# Sheet3.net
KiCad netlist of a schematic drawn in Altium Designer
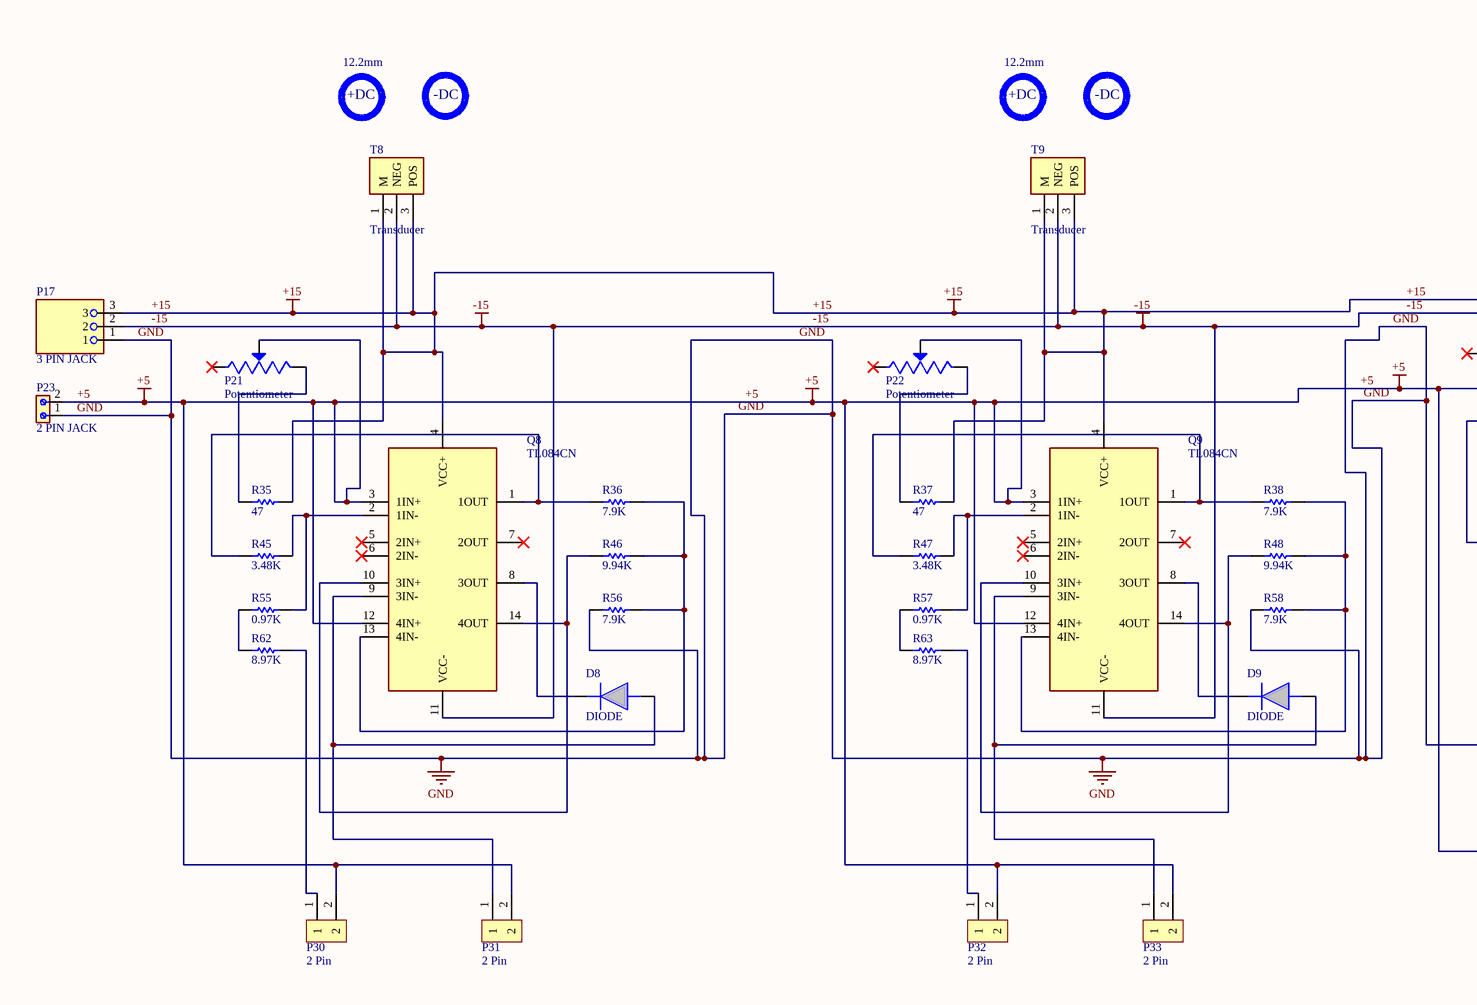
[diagram p0: Sheet3.SchDoc, left]
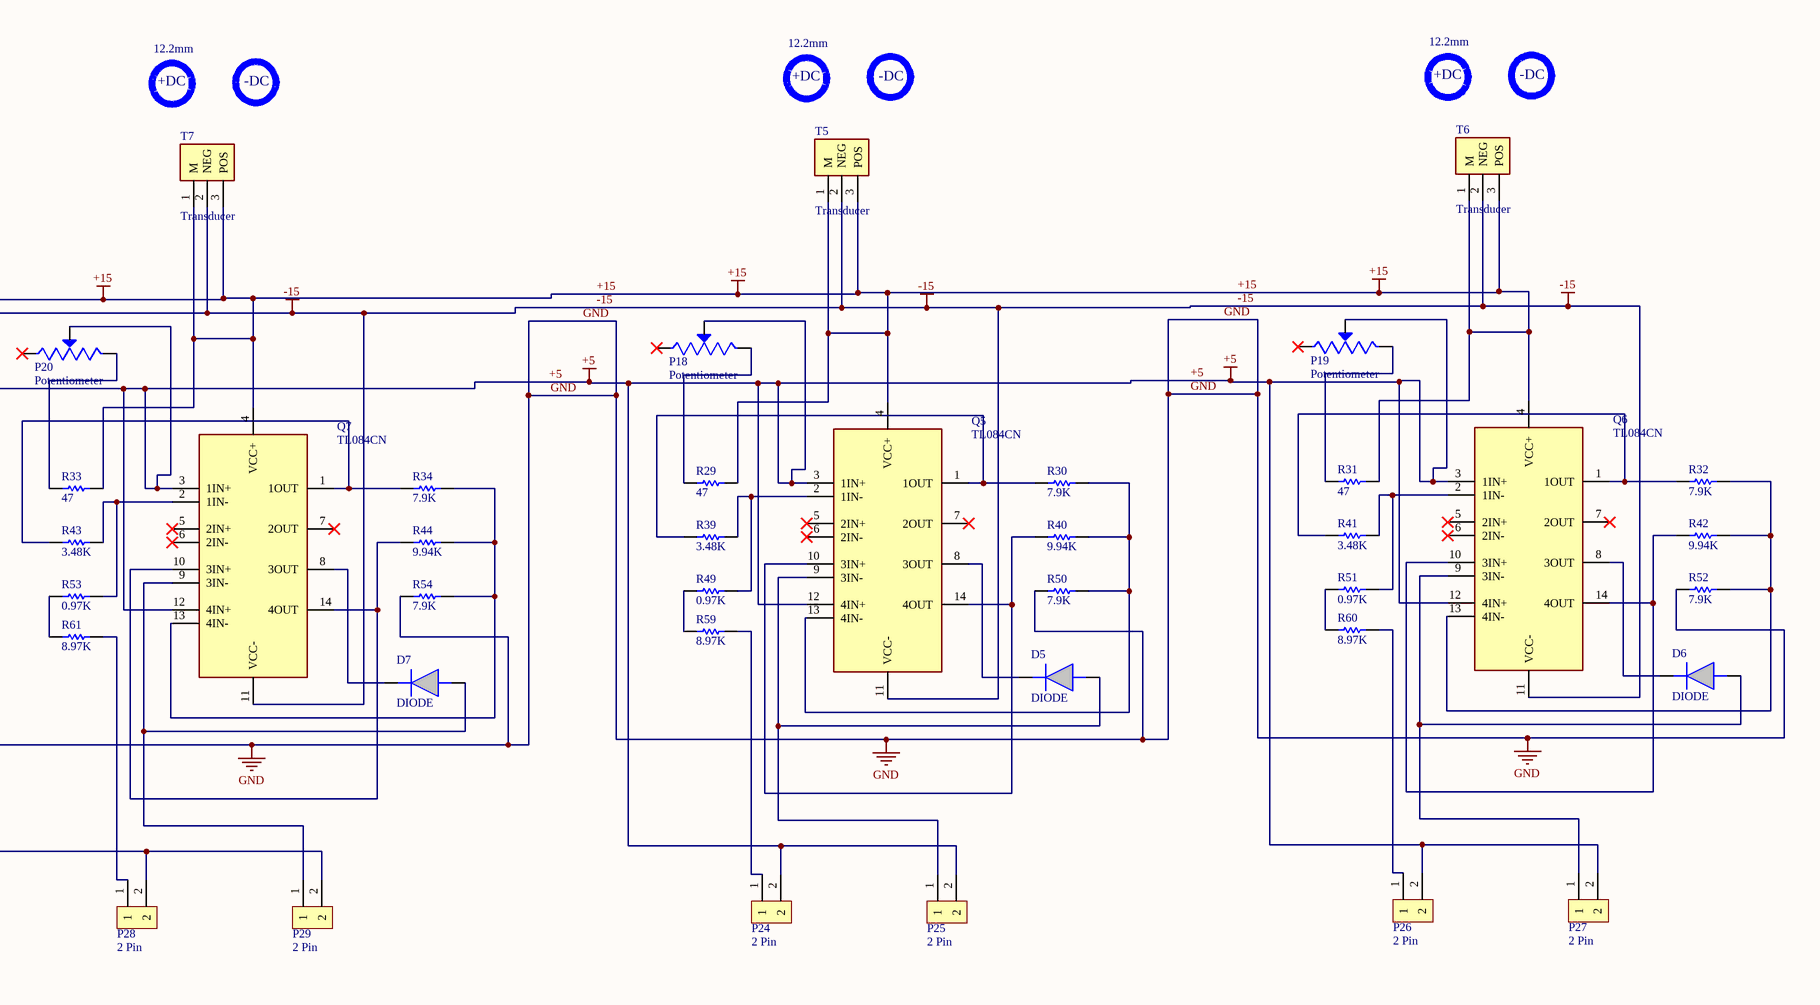
[diagram p1: Sheet3.SchDoc, right]

(export (version "E")
  (design (tool "Eeschema 10.0.6"))
  (components
    (comp (ref "D5")
      (value "DIODE")
      (footprint "Diode")
      (description "1N4007S")
      (libsource (lib "Schlib1") (part "DIODE"))
    )
    (comp (ref "D6")
      (value "DIODE")
      (footprint "Diode")
      (description "1N4007S")
      (libsource (lib "Schlib1") (part "DIODE"))
    )
    (comp (ref "D7")
      (value "DIODE")
      (footprint "Diode")
      (description "1N4007S")
      (libsource (lib "Schlib1") (part "DIODE"))
    )
    (comp (ref "D8")
      (value "DIODE")
      (footprint "Diode")
      (description "1N4007S")
      (libsource (lib "Schlib1") (part "DIODE"))
    )
    (comp (ref "D9")
      (value "DIODE")
      (footprint "Diode")
      (description "1N4007S")
      (libsource (lib "Schlib1") (part "DIODE"))
    )
    (comp (ref "P17")
      (value "3 PIN JACK")
      (footprint "3 PIN JACK")
      (libsource (lib "Schlib1") (part "3 PIN JACK"))
    )
    (comp (ref "P18")
      (value "Potentiometer")
      (footprint "Potentiometer")
      (libsource (lib "Schlib1") (part "Potentiometer"))
    )
    (comp (ref "P19")
      (value "Potentiometer")
      (footprint "Potentiometer")
      (libsource (lib "Schlib1") (part "Potentiometer"))
    )
    (comp (ref "P20")
      (value "Potentiometer")
      (footprint "Potentiometer")
      (libsource (lib "Schlib1") (part "Potentiometer"))
    )
    (comp (ref "P21")
      (value "Potentiometer")
      (footprint "Potentiometer")
      (libsource (lib "Schlib1") (part "Potentiometer"))
    )
    (comp (ref "P22")
      (value "Potentiometer")
      (footprint "Potentiometer")
      (libsource (lib "Schlib1") (part "Potentiometer"))
    )
    (comp (ref "P23")
      (value "2 PIN JACK")
      (footprint "2 PIN JACK")
      (libsource (lib "Schlib1") (part "2 PIN JACK"))
    )
    (comp (ref "P24")
      (value "2 Pin")
      (footprint "2 PIN")
      (description "22272021")
      (libsource (lib "Schlib1") (part "2 Pin"))
    )
    (comp (ref "P25")
      (value "2 Pin")
      (footprint "2 PIN")
      (description "22272021")
      (libsource (lib "Schlib1") (part "2 Pin"))
    )
    (comp (ref "P26")
      (value "2 Pin")
      (footprint "2 PIN")
      (description "22272021")
      (libsource (lib "Schlib1") (part "2 Pin"))
    )
    (comp (ref "P27")
      (value "2 Pin")
      (footprint "2 PIN")
      (description "22272021")
      (libsource (lib "Schlib1") (part "2 Pin"))
    )
    (comp (ref "P28")
      (value "2 Pin")
      (footprint "2 PIN")
      (description "22272021")
      (libsource (lib "Schlib1") (part "2 Pin"))
    )
    (comp (ref "P29")
      (value "2 Pin")
      (footprint "2 PIN")
      (description "22272021")
      (libsource (lib "Schlib1") (part "2 Pin"))
    )
    (comp (ref "P30")
      (value "2 Pin")
      (footprint "2 PIN")
      (description "22272021")
      (libsource (lib "Schlib1") (part "2 Pin"))
    )
    (comp (ref "P31")
      (value "2 Pin")
      (footprint "2 PIN")
      (description "22272021")
      (libsource (lib "Schlib1") (part "2 Pin"))
    )
    (comp (ref "P32")
      (value "2 Pin")
      (footprint "2 PIN")
      (description "22272021")
      (libsource (lib "Schlib1") (part "2 Pin"))
    )
    (comp (ref "P33")
      (value "2 Pin")
      (footprint "2 PIN")
      (description "22272021")
      (libsource (lib "Schlib1") (part "2 Pin"))
    )
    (comp (ref "Q5") (value "TL084CN") (footprint "TL084CN") (libsource (lib "Schlib1") (part "TL084CN")))
    (comp (ref "Q6") (value "TL084CN") (footprint "TL084CN") (libsource (lib "Schlib1") (part "TL084CN")))
    (comp (ref "Q7") (value "TL084CN") (footprint "TL084CN") (libsource (lib "Schlib1") (part "TL084CN")))
    (comp (ref "Q8") (value "TL084CN") (footprint "TL084CN") (libsource (lib "Schlib1") (part "TL084CN")))
    (comp (ref "Q9") (value "TL084CN") (footprint "TL084CN") (libsource (lib "Schlib1") (part "TL084CN")))
    (comp (ref "R29")
      (value "47")
      (footprint "47")
      (description "MFR-25FRF52-47R")
      (libsource (lib "Schlib1") (part "47"))
    )
    (comp (ref "R30")
      (value "7.9K")
      (footprint "7.90K")
      (description "MFR-25FBF52-7K87")
      (libsource (lib "Schlib1") (part "7.9K"))
    )
    (comp (ref "R31")
      (value "47")
      (footprint "47")
      (description "MFR-25FRF52-47R")
      (libsource (lib "Schlib1") (part "47"))
    )
    (comp (ref "R32")
      (value "7.9K")
      (footprint "7.90K")
      (description "MFR-25FBF52-7K87")
      (libsource (lib "Schlib1") (part "7.9K"))
    )
    (comp (ref "R33")
      (value "47")
      (footprint "47")
      (description "MFR-25FRF52-47R")
      (libsource (lib "Schlib1") (part "47"))
    )
    (comp (ref "R34")
      (value "7.9K")
      (footprint "7.90K")
      (description "MFR-25FBF52-7K87")
      (libsource (lib "Schlib1") (part "7.9K"))
    )
    (comp (ref "R35")
      (value "47")
      (footprint "47")
      (description "MFR-25FRF52-47R")
      (libsource (lib "Schlib1") (part "47"))
    )
    (comp (ref "R36")
      (value "7.9K")
      (footprint "7.90K")
      (description "MFR-25FBF52-7K87")
      (libsource (lib "Schlib1") (part "7.9K"))
    )
    (comp (ref "R37")
      (value "47")
      (footprint "47")
      (description "MFR-25FRF52-47R")
      (libsource (lib "Schlib1") (part "47"))
    )
    (comp (ref "R38")
      (value "7.9K")
      (footprint "7.90K")
      (description "MFR-25FBF52-7K87")
      (libsource (lib "Schlib1") (part "7.9K"))
    )
    (comp (ref "R39")
      (value "3.48K")
      (footprint "3.48K")
      (description "MFR-25FBF52-3K48")
      (libsource (lib "Schlib1") (part "3.48K"))
    )
    (comp (ref "R40")
      (value "9.94K")
      (footprint "9.94K")
      (description "MFR-25FTE52-9K76")
      (libsource (lib "Schlib1") (part "9.94K"))
    )
    (comp (ref "R41")
      (value "3.48K")
      (footprint "3.48K")
      (description "MFR-25FBF52-3K48")
      (libsource (lib "Schlib1") (part "3.48K"))
    )
    (comp (ref "R42")
      (value "9.94K")
      (footprint "9.94K")
      (description "MFR-25FTE52-9K76")
      (libsource (lib "Schlib1") (part "9.94K"))
    )
    (comp (ref "R43")
      (value "3.48K")
      (footprint "3.48K")
      (description "MFR-25FBF52-3K48")
      (libsource (lib "Schlib1") (part "3.48K"))
    )
    (comp (ref "R44")
      (value "9.94K")
      (footprint "9.94K")
      (description "MFR-25FTE52-9K76")
      (libsource (lib "Schlib1") (part "9.94K"))
    )
    (comp (ref "R45")
      (value "3.48K")
      (footprint "3.48K")
      (description "MFR-25FBF52-3K48")
      (libsource (lib "Schlib1") (part "3.48K"))
    )
    (comp (ref "R46")
      (value "9.94K")
      (footprint "9.94K")
      (description "MFR-25FTE52-9K76")
      (libsource (lib "Schlib1") (part "9.94K"))
    )
    (comp (ref "R47")
      (value "3.48K")
      (footprint "3.48K")
      (description "MFR-25FBF52-3K48")
      (libsource (lib "Schlib1") (part "3.48K"))
    )
    (comp (ref "R48")
      (value "9.94K")
      (footprint "9.94K")
      (description "MFR-25FTE52-9K76")
      (libsource (lib "Schlib1") (part "9.94K"))
    )
    (comp (ref "R49")
      (value "0.97K")
      (footprint "0.97K")
      (description "MFR-25FRF52-976R")
      (libsource (lib "Schlib1") (part "0.97K"))
    )
    (comp (ref "R50")
      (value "7.9K")
      (footprint "7.90K")
      (description "MFR-25FBF52-7K87")
      (libsource (lib "Schlib1") (part "7.9K"))
    )
    (comp (ref "R51")
      (value "0.97K")
      (footprint "0.97K")
      (description "MFR-25FRF52-976R")
      (libsource (lib "Schlib1") (part "0.97K"))
    )
    (comp (ref "R52")
      (value "7.9K")
      (footprint "7.90K")
      (description "MFR-25FBF52-7K87")
      (libsource (lib "Schlib1") (part "7.9K"))
    )
    (comp (ref "R53")
      (value "0.97K")
      (footprint "0.97K")
      (description "MFR-25FRF52-976R")
      (libsource (lib "Schlib1") (part "0.97K"))
    )
    (comp (ref "R54")
      (value "7.9K")
      (footprint "7.90K")
      (description "MFR-25FBF52-7K87")
      (libsource (lib "Schlib1") (part "7.9K"))
    )
    (comp (ref "R55")
      (value "0.97K")
      (footprint "0.97K")
      (description "MFR-25FRF52-976R")
      (libsource (lib "Schlib1") (part "0.97K"))
    )
    (comp (ref "R56")
      (value "7.9K")
      (footprint "7.90K")
      (description "MFR-25FBF52-7K87")
      (libsource (lib "Schlib1") (part "7.9K"))
    )
    (comp (ref "R57")
      (value "0.97K")
      (footprint "0.97K")
      (description "MFR-25FRF52-976R")
      (libsource (lib "Schlib1") (part "0.97K"))
    )
    (comp (ref "R58")
      (value "7.9K")
      (footprint "7.90K")
      (description "MFR-25FBF52-7K87")
      (libsource (lib "Schlib1") (part "7.9K"))
    )
    (comp (ref "R59")
      (value "8.97K")
      (footprint "8.97K")
      (description "MFR-25FBF52-8K87")
      (libsource (lib "Schlib1") (part "8.97K"))
    )
    (comp (ref "R60")
      (value "8.97K")
      (footprint "8.97K")
      (description "MFR-25FBF52-8K87")
      (libsource (lib "Schlib1") (part "8.97K"))
    )
    (comp (ref "R61")
      (value "8.97K")
      (footprint "8.97K")
      (description "MFR-25FBF52-8K87")
      (libsource (lib "Schlib1") (part "8.97K"))
    )
    (comp (ref "R62")
      (value "8.97K")
      (footprint "8.97K")
      (description "MFR-25FBF52-8K87")
      (libsource (lib "Schlib1") (part "8.97K"))
    )
    (comp (ref "R63")
      (value "8.97K")
      (footprint "8.97K")
      (description "MFR-25FBF52-8K87")
      (libsource (lib "Schlib1") (part "8.97K"))
    )
    (comp (ref "T5")
      (value "Transducer")
      (footprint "Transducer")
      (description "LA55-P")
      (libsource (lib "Schlib1") (part "Transducer"))
    )
    (comp (ref "T6")
      (value "Transducer")
      (footprint "Transducer")
      (description "LA55-P")
      (libsource (lib "Schlib1") (part "Transducer"))
    )
    (comp (ref "T7")
      (value "Transducer")
      (footprint "Transducer")
      (description "LA55-P")
      (libsource (lib "Schlib1") (part "Transducer"))
    )
    (comp (ref "T8")
      (value "Transducer")
      (footprint "Transducer")
      (description "LA55-P")
      (libsource (lib "Schlib1") (part "Transducer"))
    )
    (comp (ref "T9")
      (value "Transducer")
      (footprint "Transducer")
      (description "LA55-P")
      (libsource (lib "Schlib1") (part "Transducer"))
    )
  )
  (nets
    (net (code "1") (name "+5") (class "Default")
      (node (ref "P18") (pin "2") (pinfunction "WIPER_2") (pintype "passive"))
      (node (ref "P19") (pin "2") (pinfunction "WIPER_2") (pintype "passive"))
      (node (ref "P20") (pin "2") (pinfunction "WIPER_2") (pintype "passive"))
      (node (ref "P21") (pin "2") (pinfunction "WIPER_2") (pintype "passive"))
      (node (ref "P22") (pin "2") (pinfunction "WIPER_2") (pintype "passive"))
      (node (ref "P23") (pin "2") (pinfunction "2_2") (pintype "passive"))
      (node (ref "P24") (pin "2") (pinfunction "2_2") (pintype "passive"))
      (node (ref "P25") (pin "2") (pinfunction "2_2") (pintype "passive"))
      (node (ref "P26") (pin "2") (pinfunction "2_2") (pintype "passive"))
      (node (ref "P27") (pin "2") (pinfunction "2_2") (pintype "passive"))
      (node (ref "P28") (pin "2") (pinfunction "2_2") (pintype "passive"))
      (node (ref "P29") (pin "2") (pinfunction "2_2") (pintype "passive"))
      (node (ref "P30") (pin "2") (pinfunction "2_2") (pintype "passive"))
      (node (ref "P31") (pin "2") (pinfunction "2_2") (pintype "passive"))
      (node (ref "P32") (pin "2") (pinfunction "2_2") (pintype "passive"))
      (node (ref "P33") (pin "2") (pinfunction "2_2") (pintype "passive"))
      (node (ref "Q5") (pin "12") (pinfunction "4IN+_12") (pintype "passive"))
      (node (ref "Q5") (pin "3") (pinfunction "1IN+_3") (pintype "passive"))
      (node (ref "Q6") (pin "12") (pinfunction "4IN+_12") (pintype "passive"))
      (node (ref "Q6") (pin "3") (pinfunction "1IN+_3") (pintype "passive"))
      (node (ref "Q7") (pin "12") (pinfunction "4IN+_12") (pintype "passive"))
      (node (ref "Q7") (pin "3") (pinfunction "1IN+_3") (pintype "passive"))
      (node (ref "Q8") (pin "12") (pinfunction "4IN+_12") (pintype "passive"))
      (node (ref "Q8") (pin "3") (pinfunction "1IN+_3") (pintype "passive"))
      (node (ref "Q9") (pin "12") (pinfunction "4IN+_12") (pintype "passive"))
      (node (ref "Q9") (pin "3") (pinfunction "1IN+_3") (pintype "passive"))
    )
    (net (code "2") (name "+15") (class "Default")
      (node (ref "P17") (pin "3") (pinfunction "3_3") (pintype "passive"))
      (node (ref "Q5") (pin "4") (pinfunction "VCC+_4") (pintype "power_in"))
      (node (ref "Q6") (pin "4") (pinfunction "VCC+_4") (pintype "power_in"))
      (node (ref "Q7") (pin "4") (pinfunction "VCC+_4") (pintype "power_in"))
      (node (ref "Q8") (pin "4") (pinfunction "VCC+_4") (pintype "power_in"))
      (node (ref "Q9") (pin "4") (pinfunction "VCC+_4") (pintype "power_in"))
      (node (ref "R29") (pin "2") (pinfunction "2_2") (pintype "passive"))
      (node (ref "R31") (pin "2") (pinfunction "2_2") (pintype "passive"))
      (node (ref "R33") (pin "2") (pinfunction "2_2") (pintype "passive"))
      (node (ref "R35") (pin "2") (pinfunction "2_2") (pintype "passive"))
      (node (ref "R37") (pin "2") (pinfunction "2_2") (pintype "passive"))
      (node (ref "T5") (pin "1") (pinfunction "M_1") (pintype "power_in"))
      (node (ref "T5") (pin "3") (pinfunction "POS_3") (pintype "power_in"))
      (node (ref "T6") (pin "1") (pinfunction "M_1") (pintype "power_in"))
      (node (ref "T6") (pin "3") (pinfunction "POS_3") (pintype "power_in"))
      (node (ref "T7") (pin "1") (pinfunction "M_1") (pintype "power_in"))
      (node (ref "T7") (pin "3") (pinfunction "POS_3") (pintype "power_in"))
      (node (ref "T8") (pin "1") (pinfunction "M_1") (pintype "power_in"))
      (node (ref "T8") (pin "3") (pinfunction "POS_3") (pintype "power_in"))
      (node (ref "T9") (pin "1") (pinfunction "M_1") (pintype "power_in"))
      (node (ref "T9") (pin "3") (pinfunction "POS_3") (pintype "power_in"))
    )
    (net (code "3") (name "-15") (class "Default")
      (node (ref "P17") (pin "2") (pinfunction "2_2") (pintype "passive"))
      (node (ref "Q5") (pin "11") (pinfunction "VCC-_11") (pintype "power_in"))
      (node (ref "Q6") (pin "11") (pinfunction "VCC-_11") (pintype "power_in"))
      (node (ref "Q7") (pin "11") (pinfunction "VCC-_11") (pintype "power_in"))
      (node (ref "Q8") (pin "11") (pinfunction "VCC-_11") (pintype "power_in"))
      (node (ref "Q9") (pin "11") (pinfunction "VCC-_11") (pintype "power_in"))
      (node (ref "T5") (pin "2") (pinfunction "NEG_2") (pintype "power_in"))
      (node (ref "T6") (pin "2") (pinfunction "NEG_2") (pintype "power_in"))
      (node (ref "T7") (pin "2") (pinfunction "NEG_2") (pintype "power_in"))
      (node (ref "T8") (pin "2") (pinfunction "NEG_2") (pintype "power_in"))
      (node (ref "T9") (pin "2") (pinfunction "NEG_2") (pintype "power_in"))
    )
    (net (code "4") (name "GND") (class "Default")
      (node (ref "P17") (pin "1") (pinfunction "1_1") (pintype "passive"))
      (node (ref "P23") (pin "1") (pinfunction "1_1") (pintype "passive"))
      (node (ref "R50") (pin "1") (pinfunction "1_1") (pintype "passive"))
      (node (ref "R52") (pin "1") (pinfunction "1_1") (pintype "passive"))
      (node (ref "R54") (pin "1") (pinfunction "1_1") (pintype "passive"))
      (node (ref "R56") (pin "1") (pinfunction "1_1") (pintype "passive"))
      (node (ref "R58") (pin "1") (pinfunction "1_1") (pintype "passive"))
    )
    (net (code "5") (name "Net-(D5-A)") (class "Default")
      (node (ref "D5") (pin "2") (pinfunction "A_2") (pintype "passive"))
      (node (ref "P25") (pin "1") (pinfunction "1_1") (pintype "passive"))
      (node (ref "Q5") (pin "9") (pinfunction "3IN-_9") (pintype "passive"))
    )
    (net (code "6") (name "Net-(D5-K)") (class "Default")
      (node (ref "D5") (pin "1") (pinfunction "K_1") (pintype "passive"))
      (node (ref "Q5") (pin "8") (pinfunction "3OUT_8") (pintype "passive"))
    )
    (net (code "7") (name "Net-(D6-A)") (class "Default")
      (node (ref "D6") (pin "2") (pinfunction "A_2") (pintype "passive"))
      (node (ref "P27") (pin "1") (pinfunction "1_1") (pintype "passive"))
      (node (ref "Q6") (pin "9") (pinfunction "3IN-_9") (pintype "passive"))
    )
    (net (code "8") (name "Net-(D6-K)") (class "Default")
      (node (ref "D6") (pin "1") (pinfunction "K_1") (pintype "passive"))
      (node (ref "Q6") (pin "8") (pinfunction "3OUT_8") (pintype "passive"))
    )
    (net (code "9") (name "Net-(D7-A)") (class "Default")
      (node (ref "D7") (pin "2") (pinfunction "A_2") (pintype "passive"))
      (node (ref "P29") (pin "1") (pinfunction "1_1") (pintype "passive"))
      (node (ref "Q7") (pin "9") (pinfunction "3IN-_9") (pintype "passive"))
    )
    (net (code "10") (name "Net-(D7-K)") (class "Default")
      (node (ref "D7") (pin "1") (pinfunction "K_1") (pintype "passive"))
      (node (ref "Q7") (pin "8") (pinfunction "3OUT_8") (pintype "passive"))
    )
    (net (code "11") (name "Net-(D8-A)") (class "Default")
      (node (ref "D8") (pin "2") (pinfunction "A_2") (pintype "passive"))
      (node (ref "P31") (pin "1") (pinfunction "1_1") (pintype "passive"))
      (node (ref "Q8") (pin "9") (pinfunction "3IN-_9") (pintype "passive"))
    )
    (net (code "12") (name "Net-(D8-K)") (class "Default")
      (node (ref "D8") (pin "1") (pinfunction "K_1") (pintype "passive"))
      (node (ref "Q8") (pin "8") (pinfunction "3OUT_8") (pintype "passive"))
    )
    (net (code "13") (name "Net-(D9-A)") (class "Default")
      (node (ref "D9") (pin "2") (pinfunction "A_2") (pintype "passive"))
      (node (ref "P33") (pin "1") (pinfunction "1_1") (pintype "passive"))
      (node (ref "Q9") (pin "9") (pinfunction "3IN-_9") (pintype "passive"))
    )
    (net (code "14") (name "Net-(D9-K)") (class "Default")
      (node (ref "D9") (pin "1") (pinfunction "K_1") (pintype "passive"))
      (node (ref "Q9") (pin "8") (pinfunction "3OUT_8") (pintype "passive"))
    )
    (net (code "15") (name "Net-(P18-CW)") (class "Default")
      (node (ref "P18") (pin "3") (pinfunction "CW_3") (pintype "passive"))
      (node (ref "R29") (pin "1") (pinfunction "1_1") (pintype "passive"))
    )
    (net (code "16") (name "Net-(P19-CW)") (class "Default")
      (node (ref "P19") (pin "3") (pinfunction "CW_3") (pintype "passive"))
      (node (ref "R31") (pin "1") (pinfunction "1_1") (pintype "passive"))
    )
    (net (code "17") (name "Net-(P20-CW)") (class "Default")
      (node (ref "P20") (pin "3") (pinfunction "CW_3") (pintype "passive"))
      (node (ref "R33") (pin "1") (pinfunction "1_1") (pintype "passive"))
    )
    (net (code "18") (name "Net-(P21-CW)") (class "Default")
      (node (ref "P21") (pin "3") (pinfunction "CW_3") (pintype "passive"))
      (node (ref "R35") (pin "1") (pinfunction "1_1") (pintype "passive"))
    )
    (net (code "19") (name "Net-(P22-CW)") (class "Default")
      (node (ref "P22") (pin "3") (pinfunction "CW_3") (pintype "passive"))
      (node (ref "R37") (pin "1") (pinfunction "1_1") (pintype "passive"))
    )
    (net (code "20") (name "Net-(P24-Pad1)") (class "Default")
      (node (ref "P24") (pin "1") (pinfunction "1_1") (pintype "passive"))
      (node (ref "R59") (pin "2") (pinfunction "2_2") (pintype "passive"))
    )
    (net (code "21") (name "Net-(P26-Pad1)") (class "Default")
      (node (ref "P26") (pin "1") (pinfunction "1_1") (pintype "passive"))
      (node (ref "R60") (pin "2") (pinfunction "2_2") (pintype "passive"))
    )
    (net (code "22") (name "Net-(P28-Pad1)") (class "Default")
      (node (ref "P28") (pin "1") (pinfunction "1_1") (pintype "passive"))
      (node (ref "R61") (pin "2") (pinfunction "2_2") (pintype "passive"))
    )
    (net (code "23") (name "Net-(P30-Pad1)") (class "Default")
      (node (ref "P30") (pin "1") (pinfunction "1_1") (pintype "passive"))
      (node (ref "R62") (pin "2") (pinfunction "2_2") (pintype "passive"))
    )
    (net (code "24") (name "Net-(P32-Pad1)") (class "Default")
      (node (ref "P32") (pin "1") (pinfunction "1_1") (pintype "passive"))
      (node (ref "R63") (pin "2") (pinfunction "2_2") (pintype "passive"))
    )
    (net (code "25") (name "Net-(Q5-1IN-)") (class "Default")
      (node (ref "Q5") (pin "2") (pinfunction "1IN-_2") (pintype "passive"))
      (node (ref "R39") (pin "2") (pinfunction "2_2") (pintype "passive"))
      (node (ref "R49") (pin "2") (pinfunction "2_2") (pintype "passive"))
    )
    (net (code "26") (name "Net-(Q5-1OUT)") (class "Default")
      (node (ref "Q5") (pin "1") (pinfunction "1OUT_1") (pintype "passive"))
      (node (ref "R30") (pin "1") (pinfunction "1_1") (pintype "passive"))
      (node (ref "R39") (pin "1") (pinfunction "1_1") (pintype "passive"))
    )
    (net (code "27") (name "Net-(Q5-3IN+)") (class "Default")
      (node (ref "Q5") (pin "10") (pinfunction "3IN+_10") (pintype "passive"))
      (node (ref "Q5") (pin "14") (pinfunction "4OUT_14") (pintype "passive"))
      (node (ref "R40") (pin "1") (pinfunction "1_1") (pintype "passive"))
    )
    (net (code "28") (name "Net-(Q5-4IN-)") (class "Default")
      (node (ref "Q5") (pin "13") (pinfunction "4IN-_13") (pintype "passive"))
      (node (ref "R30") (pin "2") (pinfunction "2_2") (pintype "passive"))
      (node (ref "R40") (pin "2") (pinfunction "2_2") (pintype "passive"))
      (node (ref "R50") (pin "2") (pinfunction "2_2") (pintype "passive"))
    )
    (net (code "29") (name "Net-(Q6-1IN-)") (class "Default")
      (node (ref "Q6") (pin "2") (pinfunction "1IN-_2") (pintype "passive"))
      (node (ref "R41") (pin "2") (pinfunction "2_2") (pintype "passive"))
      (node (ref "R51") (pin "2") (pinfunction "2_2") (pintype "passive"))
    )
    (net (code "30") (name "Net-(Q6-1OUT)") (class "Default")
      (node (ref "Q6") (pin "1") (pinfunction "1OUT_1") (pintype "passive"))
      (node (ref "R32") (pin "1") (pinfunction "1_1") (pintype "passive"))
      (node (ref "R41") (pin "1") (pinfunction "1_1") (pintype "passive"))
    )
    (net (code "31") (name "Net-(Q6-3IN+)") (class "Default")
      (node (ref "Q6") (pin "10") (pinfunction "3IN+_10") (pintype "passive"))
      (node (ref "Q6") (pin "14") (pinfunction "4OUT_14") (pintype "passive"))
      (node (ref "R42") (pin "1") (pinfunction "1_1") (pintype "passive"))
    )
    (net (code "32") (name "Net-(Q6-4IN-)") (class "Default")
      (node (ref "Q6") (pin "13") (pinfunction "4IN-_13") (pintype "passive"))
      (node (ref "R32") (pin "2") (pinfunction "2_2") (pintype "passive"))
      (node (ref "R42") (pin "2") (pinfunction "2_2") (pintype "passive"))
      (node (ref "R52") (pin "2") (pinfunction "2_2") (pintype "passive"))
    )
    (net (code "33") (name "Net-(Q7-1IN-)") (class "Default")
      (node (ref "Q7") (pin "2") (pinfunction "1IN-_2") (pintype "passive"))
      (node (ref "R43") (pin "2") (pinfunction "2_2") (pintype "passive"))
      (node (ref "R53") (pin "2") (pinfunction "2_2") (pintype "passive"))
    )
    (net (code "34") (name "Net-(Q7-1OUT)") (class "Default")
      (node (ref "Q7") (pin "1") (pinfunction "1OUT_1") (pintype "passive"))
      (node (ref "R34") (pin "1") (pinfunction "1_1") (pintype "passive"))
      (node (ref "R43") (pin "1") (pinfunction "1_1") (pintype "passive"))
    )
    (net (code "35") (name "Net-(Q7-3IN+)") (class "Default")
      (node (ref "Q7") (pin "10") (pinfunction "3IN+_10") (pintype "passive"))
      (node (ref "Q7") (pin "14") (pinfunction "4OUT_14") (pintype "passive"))
      (node (ref "R44") (pin "1") (pinfunction "1_1") (pintype "passive"))
    )
    (net (code "36") (name "Net-(Q7-4IN-)") (class "Default")
      (node (ref "Q7") (pin "13") (pinfunction "4IN-_13") (pintype "passive"))
      (node (ref "R34") (pin "2") (pinfunction "2_2") (pintype "passive"))
      (node (ref "R44") (pin "2") (pinfunction "2_2") (pintype "passive"))
      (node (ref "R54") (pin "2") (pinfunction "2_2") (pintype "passive"))
    )
    (net (code "37") (name "Net-(Q8-1IN-)") (class "Default")
      (node (ref "Q8") (pin "2") (pinfunction "1IN-_2") (pintype "passive"))
      (node (ref "R45") (pin "2") (pinfunction "2_2") (pintype "passive"))
      (node (ref "R55") (pin "2") (pinfunction "2_2") (pintype "passive"))
    )
    (net (code "38") (name "Net-(Q8-1OUT)") (class "Default")
      (node (ref "Q8") (pin "1") (pinfunction "1OUT_1") (pintype "passive"))
      (node (ref "R36") (pin "1") (pinfunction "1_1") (pintype "passive"))
      (node (ref "R45") (pin "1") (pinfunction "1_1") (pintype "passive"))
    )
    (net (code "39") (name "Net-(Q8-3IN+)") (class "Default")
      (node (ref "Q8") (pin "10") (pinfunction "3IN+_10") (pintype "passive"))
      (node (ref "Q8") (pin "14") (pinfunction "4OUT_14") (pintype "passive"))
      (node (ref "R46") (pin "1") (pinfunction "1_1") (pintype "passive"))
    )
    (net (code "40") (name "Net-(Q8-4IN-)") (class "Default")
      (node (ref "Q8") (pin "13") (pinfunction "4IN-_13") (pintype "passive"))
      (node (ref "R36") (pin "2") (pinfunction "2_2") (pintype "passive"))
      (node (ref "R46") (pin "2") (pinfunction "2_2") (pintype "passive"))
      (node (ref "R56") (pin "2") (pinfunction "2_2") (pintype "passive"))
    )
    (net (code "41") (name "Net-(Q9-1IN-)") (class "Default")
      (node (ref "Q9") (pin "2") (pinfunction "1IN-_2") (pintype "passive"))
      (node (ref "R47") (pin "2") (pinfunction "2_2") (pintype "passive"))
      (node (ref "R57") (pin "2") (pinfunction "2_2") (pintype "passive"))
    )
    (net (code "42") (name "Net-(Q9-1OUT)") (class "Default")
      (node (ref "Q9") (pin "1") (pinfunction "1OUT_1") (pintype "passive"))
      (node (ref "R38") (pin "1") (pinfunction "1_1") (pintype "passive"))
      (node (ref "R47") (pin "1") (pinfunction "1_1") (pintype "passive"))
    )
    (net (code "43") (name "Net-(Q9-3IN+)") (class "Default")
      (node (ref "Q9") (pin "10") (pinfunction "3IN+_10") (pintype "passive"))
      (node (ref "Q9") (pin "14") (pinfunction "4OUT_14") (pintype "passive"))
      (node (ref "R48") (pin "1") (pinfunction "1_1") (pintype "passive"))
    )
    (net (code "44") (name "Net-(Q9-4IN-)") (class "Default")
      (node (ref "Q9") (pin "13") (pinfunction "4IN-_13") (pintype "passive"))
      (node (ref "R38") (pin "2") (pinfunction "2_2") (pintype "passive"))
      (node (ref "R48") (pin "2") (pinfunction "2_2") (pintype "passive"))
      (node (ref "R58") (pin "2") (pinfunction "2_2") (pintype "passive"))
    )
    (net (code "45") (name "Net-(R49-Pad1)") (class "Default")
      (node (ref "R49") (pin "1") (pinfunction "1_1") (pintype "passive"))
      (node (ref "R59") (pin "1") (pinfunction "1_1") (pintype "passive"))
    )
    (net (code "46") (name "Net-(R51-Pad1)") (class "Default")
      (node (ref "R51") (pin "1") (pinfunction "1_1") (pintype "passive"))
      (node (ref "R60") (pin "1") (pinfunction "1_1") (pintype "passive"))
    )
    (net (code "47") (name "Net-(R53-Pad1)") (class "Default")
      (node (ref "R53") (pin "1") (pinfunction "1_1") (pintype "passive"))
      (node (ref "R61") (pin "1") (pinfunction "1_1") (pintype "passive"))
    )
    (net (code "48") (name "Net-(R55-Pad1)") (class "Default")
      (node (ref "R55") (pin "1") (pinfunction "1_1") (pintype "passive"))
      (node (ref "R62") (pin "1") (pinfunction "1_1") (pintype "passive"))
    )
    (net (code "49") (name "Net-(R57-Pad1)") (class "Default")
      (node (ref "R57") (pin "1") (pinfunction "1_1") (pintype "passive"))
      (node (ref "R63") (pin "1") (pinfunction "1_1") (pintype "passive"))
    )
    (net (code "50") (name "unconnected-(P18-CCW-Pad1)") (class "Default")
      (node (ref "P18") (pin "1") (pinfunction "CCW_1") (pintype "passive+no_connect"))
    )
    (net (code "51") (name "unconnected-(P19-CCW-Pad1)") (class "Default")
      (node (ref "P19") (pin "1") (pinfunction "CCW_1") (pintype "passive+no_connect"))
    )
    (net (code "52") (name "unconnected-(P20-CCW-Pad1)") (class "Default")
      (node (ref "P20") (pin "1") (pinfunction "CCW_1") (pintype "passive+no_connect"))
    )
    (net (code "53") (name "unconnected-(P21-CCW-Pad1)") (class "Default")
      (node (ref "P21") (pin "1") (pinfunction "CCW_1") (pintype "passive+no_connect"))
    )
    (net (code "54") (name "unconnected-(P22-CCW-Pad1)") (class "Default")
      (node (ref "P22") (pin "1") (pinfunction "CCW_1") (pintype "passive+no_connect"))
    )
    (net (code "55") (name "unconnected-(Q5-2IN+-Pad5)") (class "Default")
      (node (ref "Q5") (pin "5") (pinfunction "2IN+_5") (pintype "passive+no_connect"))
    )
    (net (code "56") (name "unconnected-(Q5-2IN--Pad6)") (class "Default")
      (node (ref "Q5") (pin "6") (pinfunction "2IN-_6") (pintype "passive+no_connect"))
    )
    (net (code "57") (name "unconnected-(Q5-2OUT-Pad7)") (class "Default")
      (node (ref "Q5") (pin "7") (pinfunction "2OUT_7") (pintype "passive+no_connect"))
    )
    (net (code "58") (name "unconnected-(Q6-2IN+-Pad5)") (class "Default")
      (node (ref "Q6") (pin "5") (pinfunction "2IN+_5") (pintype "passive+no_connect"))
    )
    (net (code "59") (name "unconnected-(Q6-2IN--Pad6)") (class "Default")
      (node (ref "Q6") (pin "6") (pinfunction "2IN-_6") (pintype "passive+no_connect"))
    )
    (net (code "60") (name "unconnected-(Q6-2OUT-Pad7)") (class "Default")
      (node (ref "Q6") (pin "7") (pinfunction "2OUT_7") (pintype "passive+no_connect"))
    )
    (net (code "61") (name "unconnected-(Q7-2IN+-Pad5)") (class "Default")
      (node (ref "Q7") (pin "5") (pinfunction "2IN+_5") (pintype "passive+no_connect"))
    )
    (net (code "62") (name "unconnected-(Q7-2IN--Pad6)") (class "Default")
      (node (ref "Q7") (pin "6") (pinfunction "2IN-_6") (pintype "passive+no_connect"))
    )
    (net (code "63") (name "unconnected-(Q7-2OUT-Pad7)") (class "Default")
      (node (ref "Q7") (pin "7") (pinfunction "2OUT_7") (pintype "passive+no_connect"))
    )
    (net (code "64") (name "unconnected-(Q8-2IN+-Pad5)") (class "Default")
      (node (ref "Q8") (pin "5") (pinfunction "2IN+_5") (pintype "passive+no_connect"))
    )
    (net (code "65") (name "unconnected-(Q8-2IN--Pad6)") (class "Default")
      (node (ref "Q8") (pin "6") (pinfunction "2IN-_6") (pintype "passive+no_connect"))
    )
    (net (code "66") (name "unconnected-(Q8-2OUT-Pad7)") (class "Default")
      (node (ref "Q8") (pin "7") (pinfunction "2OUT_7") (pintype "passive+no_connect"))
    )
    (net (code "67") (name "unconnected-(Q9-2IN+-Pad5)") (class "Default")
      (node (ref "Q9") (pin "5") (pinfunction "2IN+_5") (pintype "passive+no_connect"))
    )
    (net (code "68") (name "unconnected-(Q9-2IN--Pad6)") (class "Default")
      (node (ref "Q9") (pin "6") (pinfunction "2IN-_6") (pintype "passive+no_connect"))
    )
    (net (code "69") (name "unconnected-(Q9-2OUT-Pad7)") (class "Default")
      (node (ref "Q9") (pin "7") (pinfunction "2OUT_7") (pintype "passive+no_connect"))
    )
  )
)
